# RAM_64K_512K.net
KiCad netlist of a schematic drawn in EAGLE
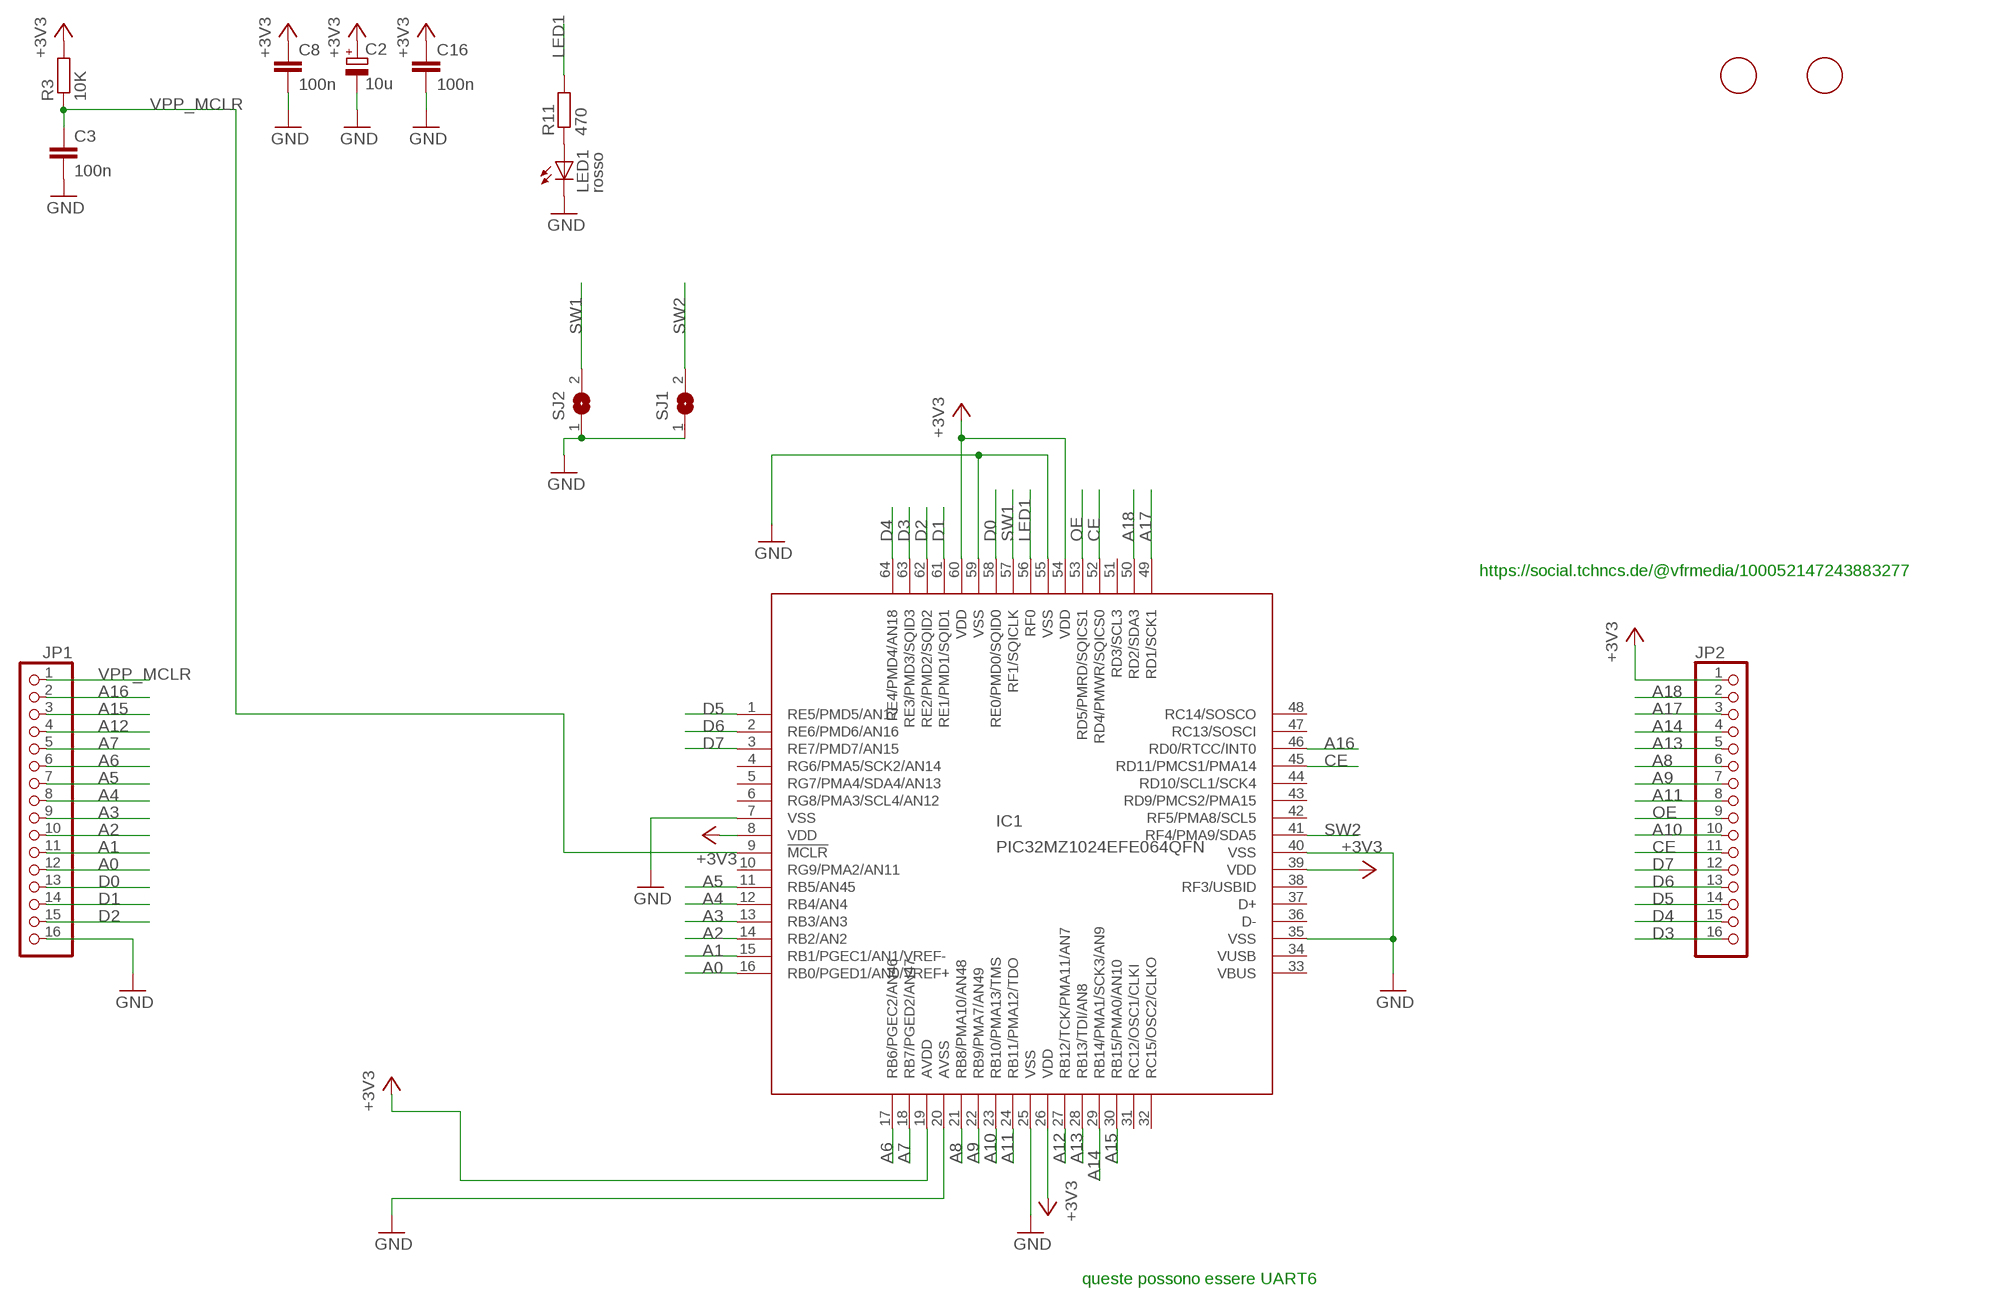
[diagram p0: schematic, sheet 1]

(export (version "E")
  (design (tool "Eeschema 10.0.6"))
  (components
    (comp (ref "C2")
      (value "10u")
      (footprint "eagle-import:SMC_B")
      (libsource (lib "eagle-import") (part "CPOL-EUSMCB"))
    )
    (comp (ref "C3")
      (value "100n")
      (footprint "eagle-import:C0805")
      (libsource (lib "eagle-import") (part "C-EUC0805"))
    )
    (comp (ref "C8")
      (value "100n")
      (footprint "eagle-import:C0805")
      (libsource (lib "eagle-import") (part "C-EUC0805"))
    )
    (comp (ref "C16")
      (value "100n")
      (footprint "eagle-import:C0805")
      (libsource (lib "eagle-import") (part "C-EUC0805"))
    )
    (comp (ref "F1")
      (value "FIDUCIAL")
      (footprint "eagle-import:FIDUCIAL_1MM")
      (libsource (lib "eagle-import") (part "FIDUCIAL"))
    )
    (comp (ref "F2")
      (value "FIDUCIAL")
      (footprint "eagle-import:FIDUCIAL_1MM")
      (libsource (lib "eagle-import") (part "FIDUCIAL"))
    )
    (comp (ref "IC1")
      (value "PIC32MZ1024EFE064QFN")
      (footprint "eagle-import:QFN64")
      (libsource (lib "eagle-import") (part "PIC32MZ1024EFE064QFN"))
    )
    (comp (ref "JP1")
      (value "PINHD-1X16_2.54")
      (footprint "eagle-import:1X16")
      (libsource (lib "eagle-import") (part "PINHD-1X16_2.54"))
    )
    (comp (ref "JP2")
      (value "PINHD-1X16_2.54")
      (footprint "eagle-import:1X16")
      (libsource (lib "eagle-import") (part "PINHD-1X16_2.54"))
    )
    (comp (ref "LED1")
      (value "rosso")
      (footprint "eagle-import:CHIPLED_0805")
      (libsource (lib "eagle-import") (part "LEDCHIPLED_0805"))
    )
    (comp (ref "R3")
      (value "10K")
      (footprint "eagle-import:R0805")
      (libsource (lib "eagle-import") (part "R-EU_R0805"))
    )
    (comp (ref "R11")
      (value "470")
      (footprint "eagle-import:R0805")
      (libsource (lib "eagle-import") (part "R-EU_R0805"))
    )
    (comp (ref "SJ1") (value "SJ") (footprint "eagle-import:SJ") (libsource (lib "eagle-import") (part "SJ")))
    (comp (ref "SJ2") (value "SJ") (footprint "eagle-import:SJ") (libsource (lib "eagle-import") (part "SJ")))
  )
  (nets
    (net (code "1") (name "+3V3") (class "Default")
      (node (ref "C16") (pin "1") (pinfunction "1_1") (pintype "passive"))
      (node (ref "C2") (pin "+") (pinfunction "+_+") (pintype "passive"))
      (node (ref "C8") (pin "1") (pinfunction "1_1") (pintype "passive"))
      (node (ref "IC1") (pin "19") (pinfunction "AVDD_19") (pintype "power_in"))
      (node (ref "IC1") (pin "26") (pinfunction "VDD_26") (pintype "power_in"))
      (node (ref "IC1") (pin "39") (pinfunction "VDD_39") (pintype "power_in"))
      (node (ref "IC1") (pin "54") (pinfunction "VDD_54") (pintype "power_in"))
      (node (ref "IC1") (pin "60") (pinfunction "VDD_60") (pintype "power_in"))
      (node (ref "IC1") (pin "8") (pinfunction "VDD_8") (pintype "power_in"))
      (node (ref "JP2") (pin "1") (pinfunction "1_1") (pintype "passive"))
      (node (ref "R3") (pin "2") (pinfunction "2_2") (pintype "passive"))
    )
    (net (code "2") (name "/A0") (class "Default")
      (node (ref "IC1") (pin "16") (pinfunction "RB0/PGED1/AN0/VREF+_16") (pintype "bidirectional"))
      (node (ref "JP1") (pin "12") (pinfunction "12_12") (pintype "passive"))
    )
    (net (code "3") (name "/A1") (class "Default")
      (node (ref "IC1") (pin "15") (pinfunction "RB1/PGEC1/AN1/VREF-_15") (pintype "bidirectional"))
      (node (ref "JP1") (pin "11") (pinfunction "11_11") (pintype "passive"))
    )
    (net (code "4") (name "/A2") (class "Default")
      (node (ref "IC1") (pin "14") (pinfunction "RB2/AN2_14") (pintype "bidirectional"))
      (node (ref "JP1") (pin "10") (pinfunction "10_10") (pintype "passive"))
    )
    (net (code "5") (name "/A3") (class "Default")
      (node (ref "IC1") (pin "13") (pinfunction "RB3/AN3_13") (pintype "bidirectional"))
      (node (ref "JP1") (pin "9") (pinfunction "9_9") (pintype "passive"))
    )
    (net (code "6") (name "/A4") (class "Default")
      (node (ref "IC1") (pin "12") (pinfunction "RB4/AN4_12") (pintype "bidirectional"))
      (node (ref "JP1") (pin "8") (pinfunction "8_8") (pintype "passive"))
    )
    (net (code "7") (name "/A5") (class "Default")
      (node (ref "IC1") (pin "11") (pinfunction "RB5/AN45_11") (pintype "bidirectional"))
      (node (ref "JP1") (pin "7") (pinfunction "7_7") (pintype "passive"))
    )
    (net (code "8") (name "/A6") (class "Default")
      (node (ref "IC1") (pin "17") (pinfunction "RB6/PGEC2/AN46_17") (pintype "bidirectional"))
      (node (ref "JP1") (pin "6") (pinfunction "6_6") (pintype "passive"))
    )
    (net (code "9") (name "/A7") (class "Default")
      (node (ref "IC1") (pin "18") (pinfunction "RB7/PGED2/AN47_18") (pintype "bidirectional"))
      (node (ref "JP1") (pin "5") (pinfunction "5_5") (pintype "passive"))
    )
    (net (code "10") (name "/A8") (class "Default")
      (node (ref "IC1") (pin "21") (pinfunction "RB8/PMA10/AN48_21") (pintype "bidirectional"))
      (node (ref "JP2") (pin "6") (pinfunction "6_6") (pintype "passive"))
    )
    (net (code "11") (name "/A9") (class "Default")
      (node (ref "IC1") (pin "22") (pinfunction "RB9/PMA7/AN49_22") (pintype "bidirectional"))
      (node (ref "JP2") (pin "7") (pinfunction "7_7") (pintype "passive"))
    )
    (net (code "12") (name "/A10") (class "Default")
      (node (ref "IC1") (pin "23") (pinfunction "RB10/PMA13/TMS_23") (pintype "bidirectional"))
      (node (ref "JP2") (pin "10") (pinfunction "10_10") (pintype "passive"))
    )
    (net (code "13") (name "/A11") (class "Default")
      (node (ref "IC1") (pin "24") (pinfunction "RB11/PMA12/TDO_24") (pintype "bidirectional"))
      (node (ref "JP2") (pin "8") (pinfunction "8_8") (pintype "passive"))
    )
    (net (code "14") (name "/A12") (class "Default")
      (node (ref "IC1") (pin "27") (pinfunction "RB12/TCK/PMA11/AN7_27") (pintype "bidirectional"))
      (node (ref "JP1") (pin "4") (pinfunction "4_4") (pintype "passive"))
    )
    (net (code "15") (name "/A13") (class "Default")
      (node (ref "IC1") (pin "28") (pinfunction "RB13/TDI/AN8_28") (pintype "bidirectional"))
      (node (ref "JP2") (pin "5") (pinfunction "5_5") (pintype "passive"))
    )
    (net (code "16") (name "/A14") (class "Default")
      (node (ref "IC1") (pin "29") (pinfunction "RB14/PMA1/SCK3/AN9_29") (pintype "bidirectional"))
      (node (ref "JP2") (pin "4") (pinfunction "4_4") (pintype "passive"))
    )
    (net (code "17") (name "/A15") (class "Default")
      (node (ref "IC1") (pin "30") (pinfunction "RB15/PMA0/AN10_30") (pintype "bidirectional"))
      (node (ref "JP1") (pin "3") (pinfunction "3_3") (pintype "passive"))
    )
    (net (code "18") (name "/A16") (class "Default")
      (node (ref "IC1") (pin "46") (pinfunction "RD0/RTCC/INT0_46") (pintype "bidirectional"))
      (node (ref "JP1") (pin "2") (pinfunction "2_2") (pintype "passive"))
    )
    (net (code "19") (name "/A17") (class "Default")
      (node (ref "IC1") (pin "49") (pinfunction "RD1/SCK1_49") (pintype "bidirectional"))
      (node (ref "JP2") (pin "3") (pinfunction "3_3") (pintype "passive"))
    )
    (net (code "20") (name "/A18") (class "Default")
      (node (ref "IC1") (pin "50") (pinfunction "RD2/SDA3_50") (pintype "bidirectional"))
      (node (ref "JP2") (pin "2") (pinfunction "2_2") (pintype "passive"))
    )
    (net (code "21") (name "/CE") (class "Default")
      (node (ref "IC1") (pin "45") (pinfunction "RD11/PMCS1/PMA14_45") (pintype "bidirectional"))
      (node (ref "IC1") (pin "52") (pinfunction "RD4/PMWR/SQICS0_52") (pintype "bidirectional"))
      (node (ref "JP2") (pin "11") (pinfunction "11_11") (pintype "passive"))
    )
    (net (code "22") (name "/D0") (class "Default")
      (node (ref "IC1") (pin "58") (pinfunction "RE0/PMD0/SQID0_58") (pintype "bidirectional"))
      (node (ref "JP1") (pin "13") (pinfunction "13_13") (pintype "passive"))
    )
    (net (code "23") (name "/D1") (class "Default")
      (node (ref "IC1") (pin "61") (pinfunction "RE1/PMD1/SQID1_61") (pintype "bidirectional"))
      (node (ref "JP1") (pin "14") (pinfunction "14_14") (pintype "passive"))
    )
    (net (code "24") (name "/D2") (class "Default")
      (node (ref "IC1") (pin "62") (pinfunction "RE2/PMD2/SQID2_62") (pintype "bidirectional"))
      (node (ref "JP1") (pin "15") (pinfunction "15_15") (pintype "passive"))
    )
    (net (code "25") (name "/D3") (class "Default")
      (node (ref "IC1") (pin "63") (pinfunction "RE3/PMD3/SQID3_63") (pintype "bidirectional"))
      (node (ref "JP2") (pin "16") (pinfunction "16_16") (pintype "passive"))
    )
    (net (code "26") (name "/D4") (class "Default")
      (node (ref "IC1") (pin "64") (pinfunction "RE4/PMD4/AN18_64") (pintype "bidirectional"))
      (node (ref "JP2") (pin "15") (pinfunction "15_15") (pintype "passive"))
    )
    (net (code "27") (name "/D5") (class "Default")
      (node (ref "IC1") (pin "1") (pinfunction "RE5/PMD5/AN17_1") (pintype "bidirectional"))
      (node (ref "JP2") (pin "14") (pinfunction "14_14") (pintype "passive"))
    )
    (net (code "28") (name "/D6") (class "Default")
      (node (ref "IC1") (pin "2") (pinfunction "RE6/PMD6/AN16_2") (pintype "bidirectional"))
      (node (ref "JP2") (pin "13") (pinfunction "13_13") (pintype "passive"))
    )
    (net (code "29") (name "/D7") (class "Default")
      (node (ref "IC1") (pin "3") (pinfunction "RE7/PMD7/AN15_3") (pintype "bidirectional"))
      (node (ref "JP2") (pin "12") (pinfunction "12_12") (pintype "passive"))
    )
    (net (code "30") (name "/LED1") (class "Default")
      (node (ref "IC1") (pin "56") (pinfunction "RF0_56") (pintype "bidirectional"))
      (node (ref "R11") (pin "2") (pinfunction "2_2") (pintype "passive"))
    )
    (net (code "31") (name "/OE") (class "Default")
      (node (ref "IC1") (pin "53") (pinfunction "RD5/PMRD/SQICS1_53") (pintype "bidirectional"))
      (node (ref "JP2") (pin "9") (pinfunction "9_9") (pintype "passive"))
    )
    (net (code "32") (name "/SW1") (class "Default")
      (node (ref "IC1") (pin "57") (pinfunction "RF1/SQICLK_57") (pintype "bidirectional"))
      (node (ref "SJ2") (pin "2") (pinfunction "2_2") (pintype "passive"))
    )
    (net (code "33") (name "/SW2") (class "Default")
      (node (ref "IC1") (pin "41") (pinfunction "RF4/PMA9/SDA5_41") (pintype "bidirectional"))
      (node (ref "SJ1") (pin "2") (pinfunction "2_2") (pintype "passive"))
    )
    (net (code "34") (name "/VPP_MCLR") (class "Default")
      (node (ref "C3") (pin "1") (pinfunction "1_1") (pintype "passive"))
      (node (ref "IC1") (pin "9") (pinfunction "~{MCLR}_9") (pintype "input"))
      (node (ref "JP1") (pin "1") (pinfunction "1_1") (pintype "passive"))
      (node (ref "R3") (pin "1") (pinfunction "1_1") (pintype "passive"))
    )
    (net (code "35") (name "/VUSB") (class "Default")
      (node (ref "IC1") (pin "34") (pinfunction "VUSB_34") (pintype "power_in"))
    )
    (net (code "36") (name "GND") (class "Default")
      (node (ref "C16") (pin "2") (pinfunction "2_2") (pintype "passive"))
      (node (ref "C2") (pin "-") (pinfunction "-_-") (pintype "passive"))
      (node (ref "C3") (pin "2") (pinfunction "2_2") (pintype "passive"))
      (node (ref "C8") (pin "2") (pinfunction "2_2") (pintype "passive"))
      (node (ref "IC1") (pin "20") (pinfunction "AVSS_20") (pintype "power_in"))
      (node (ref "IC1") (pin "25") (pinfunction "VSS_25") (pintype "power_in"))
      (node (ref "IC1") (pin "35") (pinfunction "VSS_35") (pintype "power_in"))
      (node (ref "IC1") (pin "40") (pinfunction "VSS_40") (pintype "power_in"))
      (node (ref "IC1") (pin "55") (pinfunction "VSS_55") (pintype "power_in"))
      (node (ref "IC1") (pin "59") (pinfunction "VSS_59") (pintype "power_in"))
      (node (ref "IC1") (pin "7") (pinfunction "VSS_7") (pintype "power_in"))
      (node (ref "JP1") (pin "16") (pinfunction "16_16") (pintype "passive"))
      (node (ref "LED1") (pin "C") (pinfunction "C_C") (pintype "passive"))
      (node (ref "SJ1") (pin "1") (pinfunction "1_1") (pintype "passive"))
      (node (ref "SJ2") (pin "1") (pinfunction "1_1") (pintype "passive"))
    )
    (net (code "37") (name "Net-(LED1-PadA)") (class "Default")
      (node (ref "LED1") (pin "A") (pinfunction "A_A") (pintype "passive"))
      (node (ref "R11") (pin "1") (pinfunction "1_1") (pintype "passive"))
    )
    (net (code "38") (name "unconnected-(IC1-D+-Pad37)") (class "Default")
      (node (ref "IC1") (pin "37") (pinfunction "D+_37") (pintype "passive"))
    )
    (net (code "39") (name "unconnected-(IC1-D--Pad36)") (class "Default")
      (node (ref "IC1") (pin "36") (pinfunction "D-_36") (pintype "passive"))
    )
    (net (code "40") (name "unconnected-(IC1-RC12{slash}OSC1{slash}CLKI-Pad31)") (class "Default")
      (node (ref "IC1") (pin "31") (pinfunction "RC12/OSC1/CLKI_31") (pintype "bidirectional"))
    )
    (net (code "41") (name "unconnected-(IC1-RC13{slash}SOSCI-Pad47)") (class "Default")
      (node (ref "IC1") (pin "47") (pinfunction "RC13/SOSCI_47") (pintype "bidirectional"))
    )
    (net (code "42") (name "unconnected-(IC1-RC14{slash}SOSCO-Pad48)") (class "Default")
      (node (ref "IC1") (pin "48") (pinfunction "RC14/SOSCO_48") (pintype "bidirectional"))
    )
    (net (code "43") (name "unconnected-(IC1-RC15{slash}OSC2{slash}CLKO-Pad32)") (class "Default")
      (node (ref "IC1") (pin "32") (pinfunction "RC15/OSC2/CLKO_32") (pintype "bidirectional"))
    )
    (net (code "44") (name "unconnected-(IC1-RD3{slash}SCL3-Pad51)") (class "Default")
      (node (ref "IC1") (pin "51") (pinfunction "RD3/SCL3_51") (pintype "bidirectional"))
    )
    (net (code "45") (name "unconnected-(IC1-RD9{slash}PMCS2{slash}PMA15-Pad43)") (class "Default")
      (node (ref "IC1") (pin "43") (pinfunction "RD9/PMCS2/PMA15_43") (pintype "bidirectional"))
    )
    (net (code "46") (name "unconnected-(IC1-RD10{slash}SCL1{slash}SCK4-Pad44)") (class "Default")
      (node (ref "IC1") (pin "44") (pinfunction "RD10/SCL1/SCK4_44") (pintype "bidirectional"))
    )
    (net (code "47") (name "unconnected-(IC1-RF3{slash}USBID-Pad38)") (class "Default")
      (node (ref "IC1") (pin "38") (pinfunction "RF3/USBID_38") (pintype "bidirectional"))
    )
    (net (code "48") (name "unconnected-(IC1-RF5{slash}PMA8{slash}SCL5-Pad42)") (class "Default")
      (node (ref "IC1") (pin "42") (pinfunction "RF5/PMA8/SCL5_42") (pintype "bidirectional"))
    )
    (net (code "49") (name "unconnected-(IC1-RG6{slash}PMA5{slash}SCK2{slash}AN14-Pad4)") (class "Default")
      (node (ref "IC1") (pin "4") (pinfunction "RG6/PMA5/SCK2/AN14_4") (pintype "bidirectional"))
    )
    (net (code "50") (name "unconnected-(IC1-RG7{slash}PMA4{slash}SDA4{slash}AN13-Pad5)") (class "Default")
      (node (ref "IC1") (pin "5") (pinfunction "RG7/PMA4/SDA4/AN13_5") (pintype "bidirectional"))
    )
    (net (code "51") (name "unconnected-(IC1-RG8{slash}PMA3{slash}SCL4{slash}AN12-Pad6)") (class "Default")
      (node (ref "IC1") (pin "6") (pinfunction "RG8/PMA3/SCL4/AN12_6") (pintype "bidirectional"))
    )
    (net (code "52") (name "unconnected-(IC1-RG9{slash}PMA2{slash}AN11-Pad10)") (class "Default")
      (node (ref "IC1") (pin "10") (pinfunction "RG9/PMA2/AN11_10") (pintype "bidirectional"))
    )
    (net (code "53") (name "unconnected-(IC1-VBUS-Pad33)") (class "Default")
      (node (ref "IC1") (pin "33") (pinfunction "VBUS_33") (pintype "passive"))
    )
  )
)
